# s1.net
KiCad netlist of a schematic drawn in Altium Designer
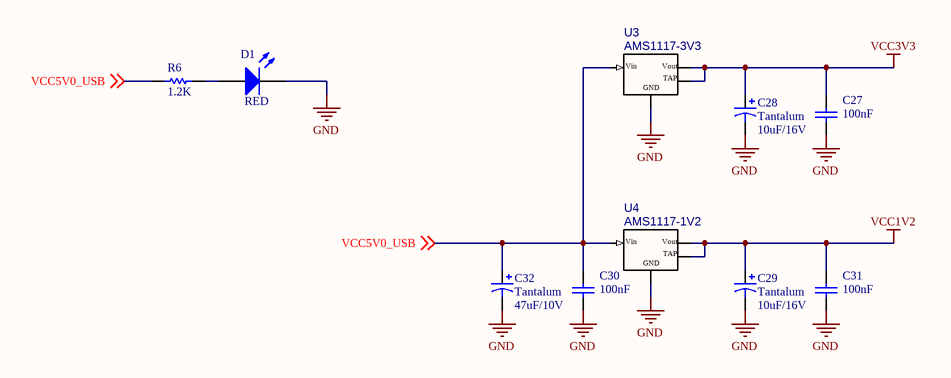
[diagram p0: s1.SchDoc]

(export (version "E")
  (design (tool "Eeschema 10.0.6"))
  (components
    (comp (ref "C27")
      (value "100nF")
      (footprint "0805 CAP")
      (description "Capacitor")
      (fields (field (name "Comment") "Cap") (field (name "PUBLISHER") "Altium Limited"))
      (libsource (lib "Miscellaneous Devices") (part "Cap"))
    )
    (comp (ref "C28")
      (value "Tantalum")
      (footprint "CT1206_TANTALUM-SMD-10UF-20V-20%(1206)(Primary)")
      (description "Polarized Capacitor (Surface Mount)")
      (fields (field (name "ALTIUM_VALUE") "10uF/16V") (field (name "PUBLISHER") "Altium Limited"))
      (libsource (lib "Miscellaneous Devices") (part "Cap Pol3"))
    )
    (comp (ref "C29")
      (value "Tantalum")
      (footprint "CT1206_TANTALUM-SMD-10UF-20V-20%(1206)(Primary)")
      (description "Polarized Capacitor (Surface Mount)")
      (fields (field (name "ALTIUM_VALUE") "10uF/16V") (field (name "PUBLISHER") "Altium Limited"))
      (libsource (lib "Miscellaneous Devices") (part "Cap Pol3"))
    )
    (comp (ref "C30")
      (value "100nF")
      (footprint "0805 CAP")
      (description "Capacitor")
      (fields (field (name "Comment") "Cap") (field (name "PUBLISHER") "Altium Limited"))
      (libsource (lib "Miscellaneous Devices") (part "Cap"))
    )
    (comp (ref "C31")
      (value "100nF")
      (footprint "0805 CAP")
      (description "Capacitor")
      (fields (field (name "Comment") "Cap") (field (name "PUBLISHER") "Altium Limited"))
      (libsource (lib "Miscellaneous Devices") (part "Cap"))
    )
    (comp (ref "C32")
      (value "Tantalum")
      (footprint "CT1206_TANTALUM-SMD-10UF-20V-20%(1206)(Primary)")
      (description "Polarized Capacitor (Surface Mount)")
      (fields (field (name "ALTIUM_VALUE") "47uF/10V") (field (name "PUBLISHER") "Altium Limited"))
      (libsource (lib "Miscellaneous Devices") (part "Cap Pol3"))
    )
    (comp (ref "D1")
      (value "RED")
      (footprint "0805 LED")
      (description "Typical INFRARED GaAs LED")
      (fields (field (name "PUBLISHER") "Altium Limited"))
      (libsource (lib "Miscellaneous Devices") (part "LED0"))
    )
    (comp (ref "R6")
      (value "1.2K")
      (footprint "0805 RES")
      (description "Resistor")
      (fields (field (name "PUBLISHER") "Altium Limited"))
      (libsource (lib "Miscellaneous Devices") (part "Res1"))
    )
    (comp (ref "U3")
      (value "AMS1117-3V3")
      (footprint "AMS1117_AMS1117(Primary)")
      (description "Integrated Circuit")
      (fields (field (name "MF") "Advanced Monolithic Systems") (field (name "MP") "AMS1117"))
      (libsource (lib "AMS1117") (part "AMS1117"))
    )
    (comp (ref "U4")
      (value "AMS1117-1V2")
      (footprint "AMS1117_AMS1117(Primary)")
      (description "Integrated Circuit")
      (fields (field (name "MF") "Advanced Monolithic Systems") (field (name "MP") "AMS1117"))
      (libsource (lib "AMS1117") (part "AMS1117"))
    )
  )
  (nets
    (net (code "1") (name "GND") (class "Default")
      (node (ref "C27") (pin "1") (pinfunction "1_1") (pintype "passive"))
      (node (ref "C28") (pin "2") (pinfunction "2_2") (pintype "passive"))
      (node (ref "C29") (pin "2") (pinfunction "2_2") (pintype "passive"))
      (node (ref "C30") (pin "1") (pinfunction "1_1") (pintype "passive"))
      (node (ref "C31") (pin "1") (pinfunction "1_1") (pintype "passive"))
      (node (ref "C32") (pin "2") (pinfunction "2_2") (pintype "passive"))
      (node (ref "D1") (pin "2") (pinfunction "K_2") (pintype "passive"))
      (node (ref "U3") (pin "GND") (pinfunction "ADJ-GND_GND") (pintype "power_in"))
      (node (ref "U4") (pin "GND") (pinfunction "ADJ-GND_GND") (pintype "power_in"))
    )
    (net (code "2") (name "Net-(D1-A)") (class "Default")
      (node (ref "D1") (pin "1") (pinfunction "A_1") (pintype "passive"))
      (node (ref "R6") (pin "2") (pinfunction "2_2") (pintype "passive"))
    )
    (net (code "3") (name "VCC1V2") (class "Default")
      (node (ref "C29") (pin "1") (pinfunction "1_1") (pintype "passive"))
      (node (ref "C31") (pin "2") (pinfunction "2_2") (pintype "passive"))
      (node (ref "U4") (pin "HEATSINK") (pinfunction "HEATSINK_HEATSINK") (pintype "power_in"))
      (node (ref "U4") (pin "VOUT") (pinfunction "VOUT_VOUT") (pintype "power_in"))
    )
    (net (code "4") (name "VCC3V3") (class "Default")
      (node (ref "C27") (pin "2") (pinfunction "2_2") (pintype "passive"))
      (node (ref "C28") (pin "1") (pinfunction "1_1") (pintype "passive"))
      (node (ref "U3") (pin "HEATSINK") (pinfunction "HEATSINK_HEATSINK") (pintype "power_in"))
      (node (ref "U3") (pin "VOUT") (pinfunction "VOUT_VOUT") (pintype "power_in"))
    )
    (net (code "5") (name "VCC5V0_USB") (class "Default")
      (node (ref "C30") (pin "2") (pinfunction "2_2") (pintype "passive"))
      (node (ref "C32") (pin "1") (pinfunction "1_1") (pintype "passive"))
      (node (ref "R6") (pin "1") (pinfunction "1_1") (pintype "passive"))
      (node (ref "U3") (pin "VIN") (pinfunction "VIN_VIN") (pintype "input"))
      (node (ref "U4") (pin "VIN") (pinfunction "VIN_VIN") (pintype "input"))
    )
  )
)
